# FD_Capacitance_Sensor_v17.net
KiCad netlist of a schematic drawn in EAGLE
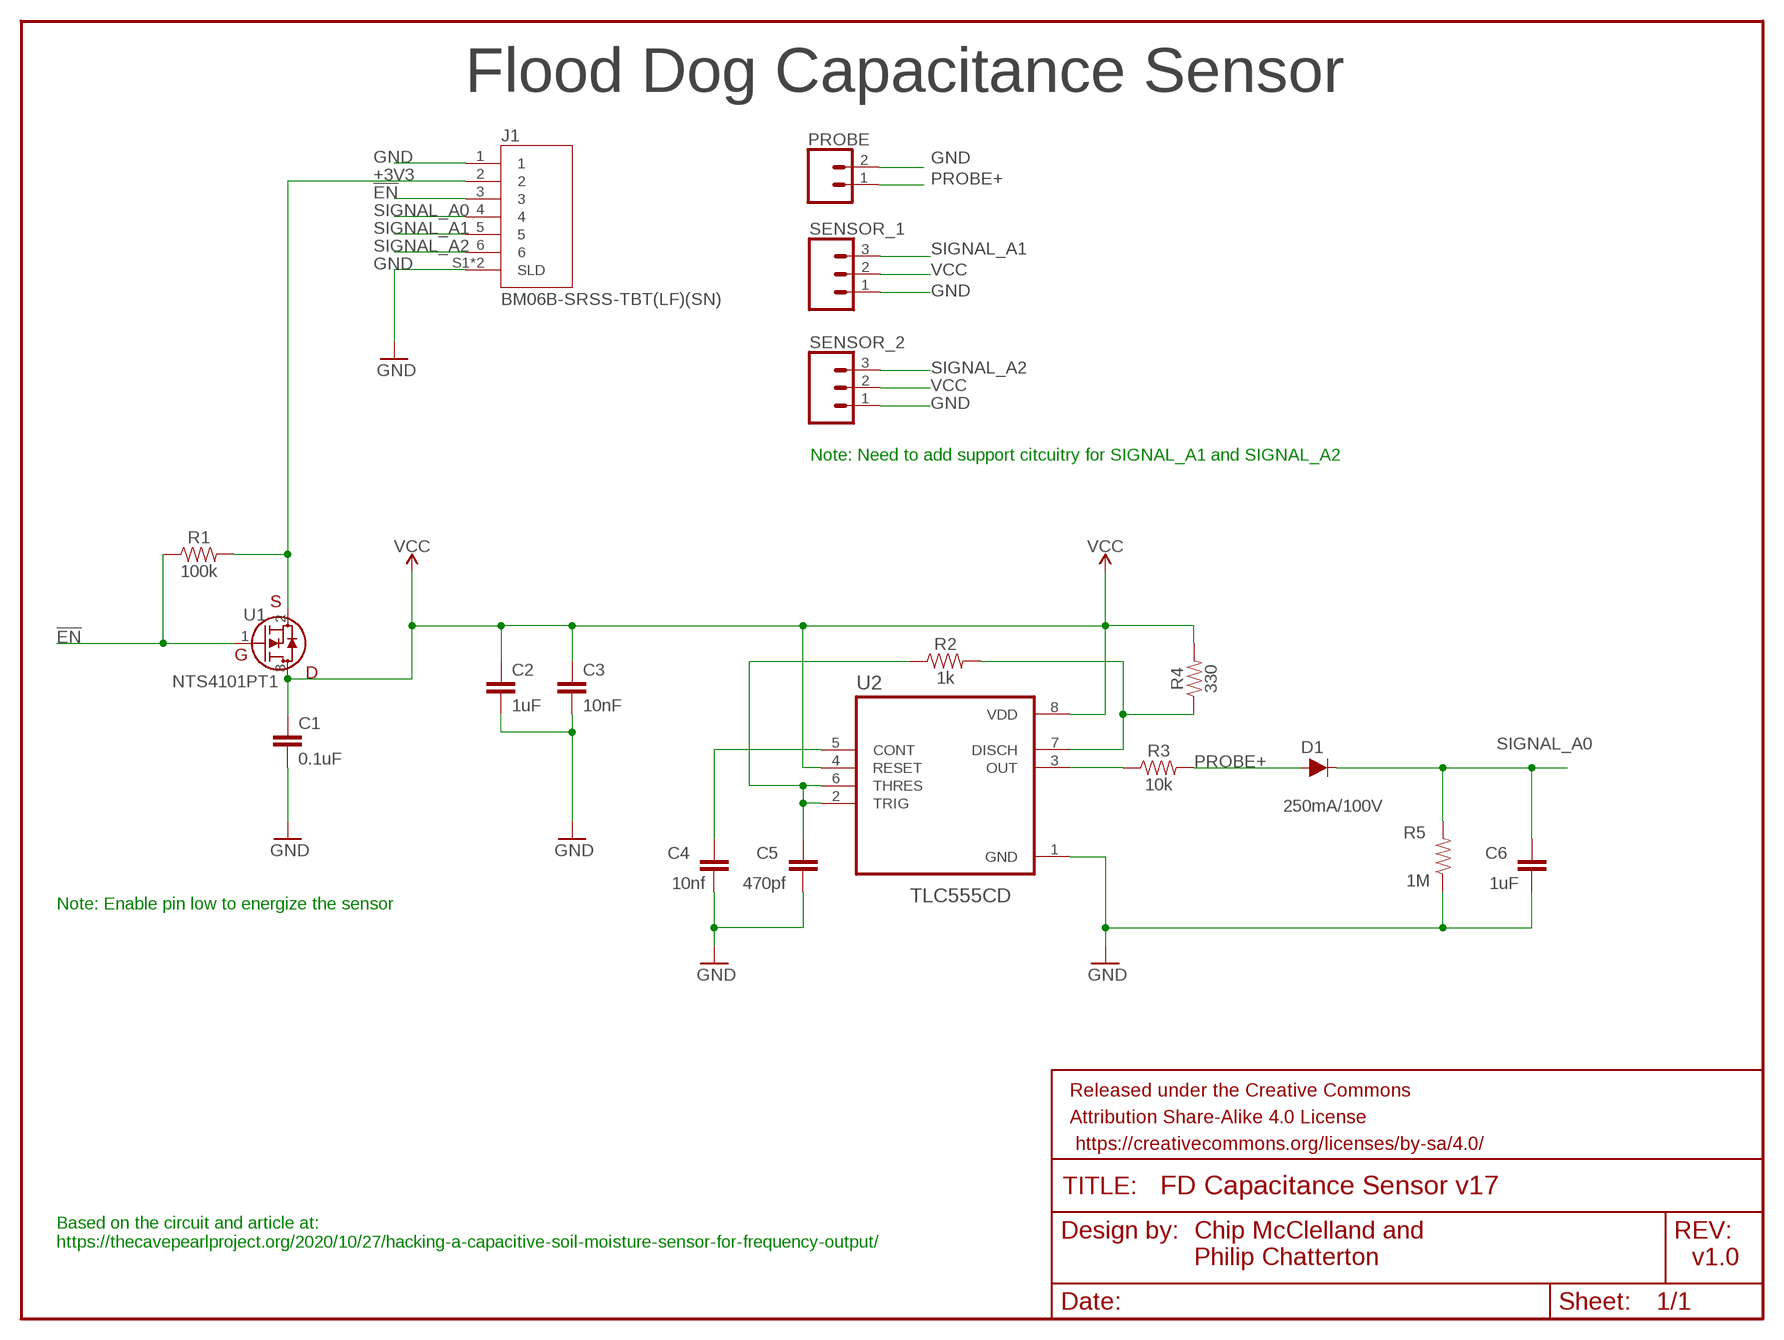
[diagram p0: schematic, sheet 1]

(export (version "E")
  (design (tool "Eeschema 10.0.6"))
  (components
    (comp (ref "C1")
      (value "0.1uF")
      (footprint "eagle-import:0805@1")
      (fields (field (name "HOUSEPART") "YES") (field (name "MPN") "MF-CAP-0805-0.1uF"))
      (libsource (lib "eagle-import") (part "CAP-MF-0.1UF-0805"))
    )
    (comp (ref "C2")
      (value "1uF")
      (footprint "eagle-import:0805@1")
      (fields (field (name "HOUSEPART") "yes") (field (name "MPN") "MF-CAP-0805-1uF"))
      (libsource (lib "eagle-import") (part "CAP-MF-1UF-0805"))
    )
    (comp (ref "C3")
      (value "10nF")
      (footprint "eagle-import:0805@1")
      (fields (field (name "HOUSEPART") "NO") (field (name "MPN") "C0805X103K1RAC3316"))
      (libsource (lib "eagle-import") (part "CAP-10NF-0805"))
    )
    (comp (ref "C4")
      (value "10nf")
      (footprint "eagle-import:C0805")
      (libsource (lib "eagle-import") (part "C-EUC0805"))
    )
    (comp (ref "C5")
      (value "470pf")
      (footprint "eagle-import:C0805")
      (libsource (lib "eagle-import") (part "C-EUC0805"))
    )
    (comp (ref "C6")
      (value "1uF")
      (footprint "eagle-import:C0805")
      (libsource (lib "eagle-import") (part "C-EUC0805"))
    )
    (comp (ref "D1")
      (value "250mA/100V")
      (footprint "eagle-import:SOD-323")
      (fields (field (name "MPN") "BAS16HT1G"))
      (libsource (lib "eagle-import") (part "DIODE-BAS16J"))
    )
    (comp (ref "FRAME1")
      (value "FRAME-LETTERNO_PACKAGE")
      (footprint "eagle-import:DUMMY")
      (fields (field (name "DESIGNER") "Nobody"))
      (libsource (lib "eagle-import") (part "FRAME-LETTERNO_PACKAGE"))
    )
    (comp (ref "J1")
      (value "BM06B-SRSS-TBT(LF)(SN)")
      (footprint "eagle-import:JST_BM06B-SRSS-TB(LF)(SN)")
      (libsource (lib "eagle-import") (part "BM06B-SRSS-TBT(LF)(SN)"))
    )
    (comp (ref "PROBE")
      (value "CONN_02")
      (footprint "eagle-import:1X02")
      (libsource (lib "eagle-import") (part "CONN_02"))
    )
    (comp (ref "R1")
      (value "100k")
      (footprint "eagle-import:0805")
      (fields (field (name "MPN") "MF-RES-0805-100K") (field (name "MPN_1") "MF-RES-0805-100K"))
      (libsource (lib "eagle-import") (part "RESISTOR-MF-100K-0805"))
    )
    (comp (ref "R2")
      (value "1k")
      (footprint "eagle-import:0805")
      (fields (field (name "HOUSEPART") "YES") (field (name "MPN") "MF-RES-0805-1K"))
      (libsource (lib "eagle-import") (part "RESISTOR-MF-1K-0805"))
    )
    (comp (ref "R3")
      (value "10k")
      (footprint "eagle-import:0805")
      (fields (field (name "MPN") "MF-RES-0805-10K"))
      (libsource (lib "eagle-import") (part "RESISTOR-MF-10K-0805"))
    )
    (comp (ref "R4")
      (value "330")
      (footprint "eagle-import:0805")
      (fields (field (name "HOUSEPART") "YES") (field (name "MPN") "MF-RES-0805-330"))
      (libsource (lib "eagle-import") (part "RESISTOR-MF-330-0805"))
    )
    (comp (ref "R5")
      (value "1M")
      (footprint "eagle-import:0805")
      (fields (field (name "HOUSEPART") "YES") (field (name "MPN") "MF-RES-0805-1K"))
      (libsource (lib "eagle-import") (part "RESISTOR-MF-1K-0805"))
    )
    (comp (ref "SENSOR_1")
      (value "CONN_03")
      (footprint "eagle-import:1X03")
      (libsource (lib "eagle-import") (part "CONN_03"))
    )
    (comp (ref "SENSOR_2")
      (value "CONN_03")
      (footprint "eagle-import:1X03")
      (libsource (lib "eagle-import") (part "CONN_03"))
    )
    (comp (ref "U1")
      (value "NTS4101PT1")
      (footprint "eagle-import:SOT_101PT1_ONS")
      (libsource (lib "eagle-import") (part "NTS4101PT1"))
    )
    (comp (ref "U2")
      (value "TLC555CD")
      (footprint "eagle-import:SOIC127P599X175-8N")
      (fields (field (name "DIGI-KEY_PART_NUMBER") "296-52992-ND") (field (name "MF") "Texas Instruments"))
      (libsource (lib "eagle-import") (part "TLC555CD"))
    )
  )
  (nets
    (net (code "1") (name "/+3V3") (class "Default")
      (node (ref "J1") (pin "2") (pinfunction "2_2") (pintype "passive"))
      (node (ref "R1") (pin "2") (pinfunction "2_2") (pintype "passive"))
      (node (ref "U1") (pin "2") (pinfunction "S_2") (pintype "passive"))
    )
    (net (code "2") (name "/PROBE+") (class "Default")
      (node (ref "D1") (pin "A") (pinfunction "A_A") (pintype "passive"))
      (node (ref "PROBE") (pin "1") (pinfunction "1_1") (pintype "passive"))
      (node (ref "R3") (pin "2") (pinfunction "2_2") (pintype "passive"))
    )
    (net (code "3") (name "/SIGNAL_A0") (class "Default")
      (node (ref "C6") (pin "2") (pinfunction "2_2") (pintype "passive"))
      (node (ref "D1") (pin "C") (pinfunction "C_C") (pintype "passive"))
      (node (ref "J1") (pin "4") (pinfunction "4_4") (pintype "passive"))
      (node (ref "R5") (pin "2") (pinfunction "2_2") (pintype "passive"))
    )
    (net (code "4") (name "/SIGNAL_A1") (class "Default")
      (node (ref "J1") (pin "5") (pinfunction "5_5") (pintype "passive"))
      (node (ref "SENSOR_1") (pin "3") (pinfunction "3_3") (pintype "passive"))
    )
    (net (code "5") (name "/SIGNAL_A2") (class "Default")
      (node (ref "J1") (pin "6") (pinfunction "6_6") (pintype "passive"))
      (node (ref "SENSOR_2") (pin "3") (pinfunction "3_3") (pintype "passive"))
    )
    (net (code "6") (name "/~{EN}") (class "Default")
      (node (ref "J1") (pin "3") (pinfunction "3_3") (pintype "passive"))
      (node (ref "R1") (pin "1") (pinfunction "1_1") (pintype "passive"))
      (node (ref "U1") (pin "1") (pinfunction "G_1") (pintype "passive"))
    )
    (net (code "7") (name "GND") (class "Default")
      (node (ref "C1") (pin "2") (pinfunction "2_2") (pintype "passive"))
      (node (ref "C2") (pin "2") (pinfunction "2_2") (pintype "passive"))
      (node (ref "C3") (pin "2") (pinfunction "2_2") (pintype "passive"))
      (node (ref "C4") (pin "1") (pinfunction "1_1") (pintype "passive"))
      (node (ref "C5") (pin "1") (pinfunction "1_1") (pintype "passive"))
      (node (ref "C6") (pin "1") (pinfunction "1_1") (pintype "passive"))
      (node (ref "J1") (pin "1") (pinfunction "1_1") (pintype "passive"))
      (node (ref "J1") (pin "S1") (pinfunction "SLD_S1") (pintype "passive"))
      (node (ref "J1") (pin "S2") (pinfunction "SLD_S2") (pintype "passive"))
      (node (ref "PROBE") (pin "2") (pinfunction "2_2") (pintype "passive"))
      (node (ref "R5") (pin "1") (pinfunction "1_1") (pintype "passive"))
      (node (ref "SENSOR_1") (pin "1") (pinfunction "1_1") (pintype "passive"))
      (node (ref "SENSOR_2") (pin "1") (pinfunction "1_1") (pintype "passive"))
      (node (ref "U2") (pin "1") (pinfunction "GND_1") (pintype "power_in"))
    )
    (net (code "8") (name "Net-(U2-CONT)") (class "Default")
      (node (ref "C4") (pin "2") (pinfunction "2_2") (pintype "passive"))
      (node (ref "U2") (pin "5") (pinfunction "CONT_5") (pintype "input"))
    )
    (net (code "9") (name "Net-(U2-DISCH)") (class "Default")
      (node (ref "R2") (pin "2") (pinfunction "2_2") (pintype "passive"))
      (node (ref "R4") (pin "1") (pinfunction "1_1") (pintype "passive"))
      (node (ref "U2") (pin "7") (pinfunction "DISCH_7") (pintype "output"))
    )
    (net (code "10") (name "Net-(U2-OUT)") (class "Default")
      (node (ref "R3") (pin "1") (pinfunction "1_1") (pintype "passive"))
      (node (ref "U2") (pin "3") (pinfunction "OUT_3") (pintype "output"))
    )
    (net (code "11") (name "Net-(U2-THRES)") (class "Default")
      (node (ref "C5") (pin "2") (pinfunction "2_2") (pintype "passive"))
      (node (ref "R2") (pin "1") (pinfunction "1_1") (pintype "passive"))
      (node (ref "U2") (pin "2") (pinfunction "TRIG_2") (pintype "input"))
      (node (ref "U2") (pin "6") (pinfunction "THRES_6") (pintype "input"))
    )
    (net (code "12") (name "VCC") (class "Default")
      (node (ref "C1") (pin "1") (pinfunction "1_1") (pintype "passive"))
      (node (ref "C2") (pin "1") (pinfunction "1_1") (pintype "passive"))
      (node (ref "C3") (pin "1") (pinfunction "1_1") (pintype "passive"))
      (node (ref "R4") (pin "2") (pinfunction "2_2") (pintype "passive"))
      (node (ref "SENSOR_1") (pin "2") (pinfunction "2_2") (pintype "passive"))
      (node (ref "SENSOR_2") (pin "2") (pinfunction "2_2") (pintype "passive"))
      (node (ref "U1") (pin "3") (pinfunction "D_3") (pintype "passive"))
      (node (ref "U2") (pin "4") (pinfunction "RESET_4") (pintype "input"))
      (node (ref "U2") (pin "8") (pinfunction "VDD_8") (pintype "power_in"))
    )
  )
)
